# huzzah32_driver.net
KiCad netlist of a schematic drawn in EAGLE
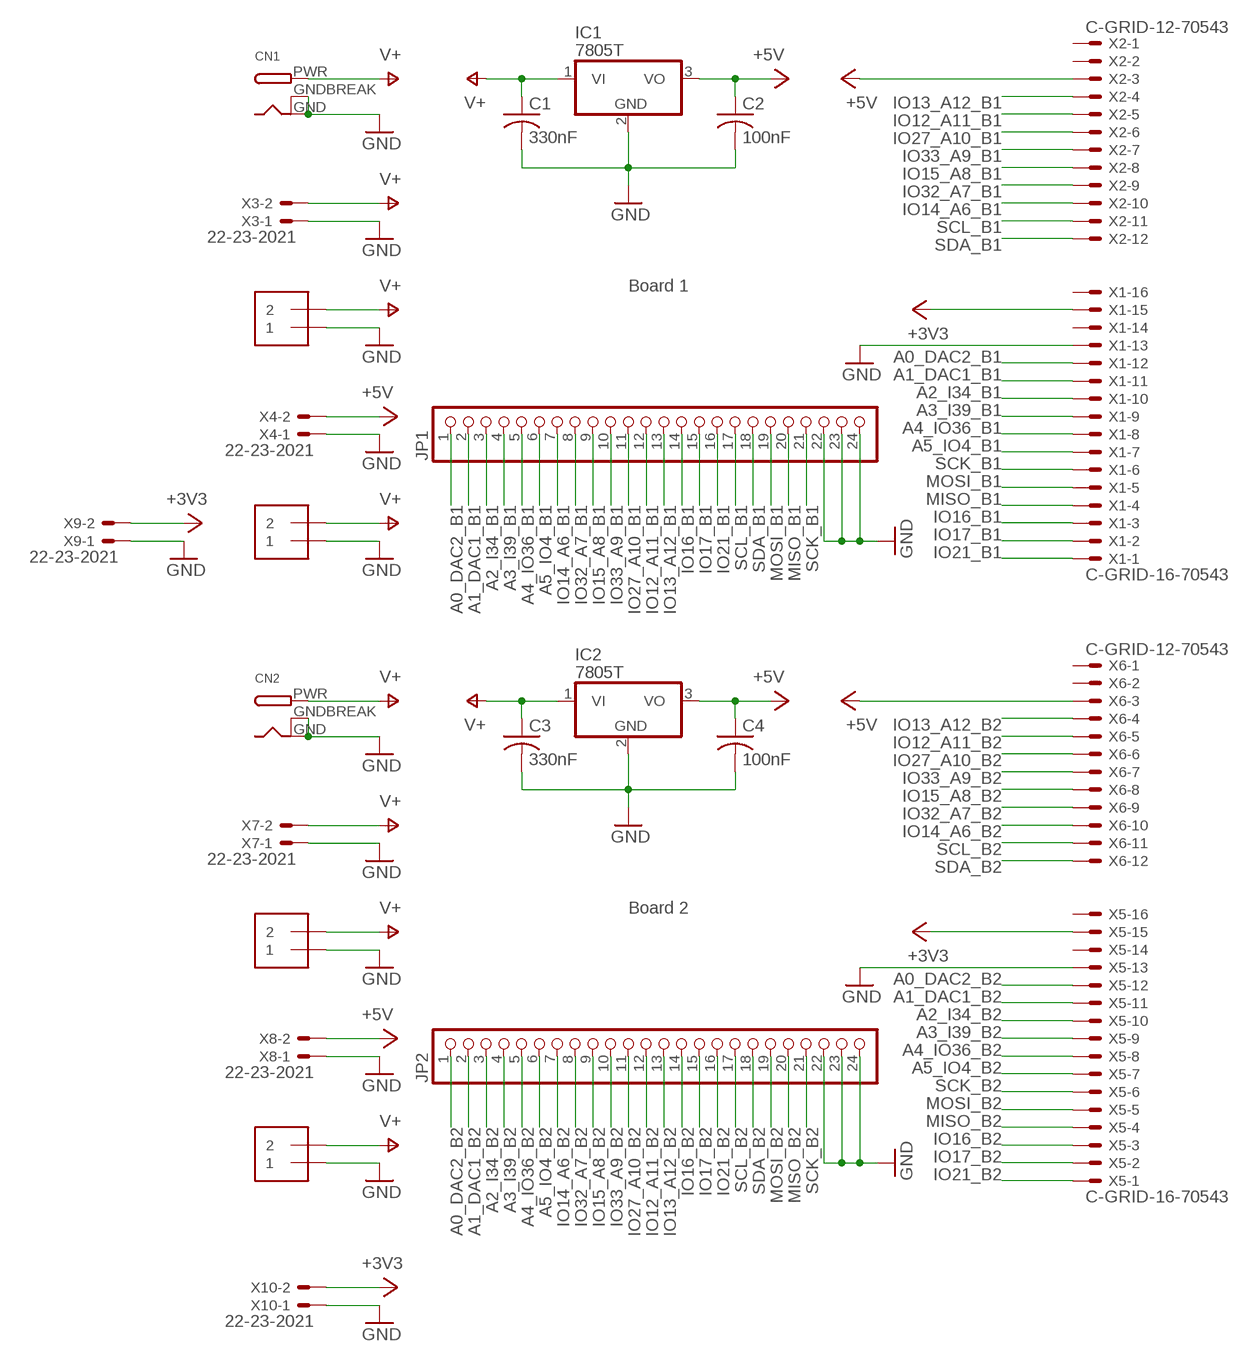
[diagram p0: schematic, sheet 1]

(export (version "E")
  (design (tool "Eeschema 10.0.6"))
  (components
    (comp (ref "C1")
      (value "330nF")
      (footprint "eagle-import:C050-035X075")
      (libsource (lib "eagle-import") (part "C-US050-035X075"))
    )
    (comp (ref "C2")
      (value "100nF")
      (footprint "eagle-import:C050-035X075")
      (libsource (lib "eagle-import") (part "C-US050-035X075"))
    )
    (comp (ref "C3")
      (value "330nF")
      (footprint "eagle-import:C050-035X075")
      (libsource (lib "eagle-import") (part "C-US050-035X075"))
    )
    (comp (ref "C4")
      (value "100nF")
      (footprint "eagle-import:C050-035X075")
      (libsource (lib "eagle-import") (part "C-US050-035X075"))
    )
    (comp (ref "CN1")
      (value "DCBARRELPTH")
      (footprint "eagle-import:DCJACK_2MM_PTH")
      (libsource (lib "eagle-import") (part "DCBARRELPTH"))
    )
    (comp (ref "CN2")
      (value "DCBARRELPTH")
      (footprint "eagle-import:DCJACK_2MM_PTH")
      (libsource (lib "eagle-import") (part "DCBARRELPTH"))
    )
    (comp (ref "IC1")
      (value "7805T")
      (footprint "eagle-import:TO220H")
      (libsource (lib "eagle-import") (part "78T05"))
    )
    (comp (ref "IC2")
      (value "7805T")
      (footprint "eagle-import:TO220H")
      (libsource (lib "eagle-import") (part "78T05"))
    )
    (comp (ref "J1")
      (value "1X2-3.5MM")
      (footprint "eagle-import:1X2-3.5MM")
      (libsource (lib "eagle-import") (part "1X2-3.5MM"))
    )
    (comp (ref "J2")
      (value "1X2-3.5MM")
      (footprint "eagle-import:1X2-3.5MM")
      (libsource (lib "eagle-import") (part "1X2-3.5MM"))
    )
    (comp (ref "J3")
      (value "1X2-3.5MM")
      (footprint "eagle-import:1X2-3.5MM")
      (libsource (lib "eagle-import") (part "1X2-3.5MM"))
    )
    (comp (ref "J4")
      (value "1X2-3.5MM")
      (footprint "eagle-import:1X2-3.5MM")
      (libsource (lib "eagle-import") (part "1X2-3.5MM"))
    )
    (comp (ref "JP1")
      (value "PINHD-1X24")
      (footprint "eagle-import:1X24")
      (libsource (lib "eagle-import") (part "PINHD-1X24"))
    )
    (comp (ref "JP2")
      (value "PINHD-1X24")
      (footprint "eagle-import:1X24")
      (libsource (lib "eagle-import") (part "PINHD-1X24"))
    )
    (comp (ref "X1")
      (value "C-GRID-16-70543")
      (footprint "eagle-import:70543-16")
      (libsource (lib "eagle-import") (part "C-GRID-16-70543"))
    )
    (comp (ref "X2")
      (value "C-GRID-12-70543")
      (footprint "eagle-import:70543-12")
      (libsource (lib "eagle-import") (part "C-GRID-12-70543"))
    )
    (comp (ref "X3")
      (value "22-23-2021")
      (footprint "eagle-import:22-23-2021")
      (fields (field (name "MF") "MOLEX"))
      (libsource (lib "eagle-import") (part "22-23-2021"))
    )
    (comp (ref "X4")
      (value "22-23-2021")
      (footprint "eagle-import:22-23-2021")
      (fields (field (name "MF") "MOLEX"))
      (libsource (lib "eagle-import") (part "22-23-2021"))
    )
    (comp (ref "X5")
      (value "C-GRID-16-70543")
      (footprint "eagle-import:70543-16")
      (libsource (lib "eagle-import") (part "C-GRID-16-70543"))
    )
    (comp (ref "X6")
      (value "C-GRID-12-70543")
      (footprint "eagle-import:70543-12")
      (libsource (lib "eagle-import") (part "C-GRID-12-70543"))
    )
    (comp (ref "X7")
      (value "22-23-2021")
      (footprint "eagle-import:22-23-2021")
      (fields (field (name "MF") "MOLEX"))
      (libsource (lib "eagle-import") (part "22-23-2021"))
    )
    (comp (ref "X8")
      (value "22-23-2021")
      (footprint "eagle-import:22-23-2021")
      (fields (field (name "MF") "MOLEX"))
      (libsource (lib "eagle-import") (part "22-23-2021"))
    )
    (comp (ref "X9")
      (value "22-23-2021")
      (footprint "eagle-import:22-23-2021")
      (fields (field (name "MF") "MOLEX"))
      (libsource (lib "eagle-import") (part "22-23-2021"))
    )
    (comp (ref "X10")
      (value "22-23-2021")
      (footprint "eagle-import:22-23-2021")
      (fields (field (name "MF") "MOLEX"))
      (libsource (lib "eagle-import") (part "22-23-2021"))
    )
  )
  (nets
    (net (code "1") (name "+3V3") (class "Default")
      (node (ref "X1") (pin "15") (pinfunction "S_15") (pintype "passive"))
      (node (ref "X10") (pin "2") (pinfunction "S_2") (pintype "passive"))
      (node (ref "X5") (pin "15") (pinfunction "S_15") (pintype "passive"))
      (node (ref "X9") (pin "2") (pinfunction "S_2") (pintype "passive"))
    )
    (net (code "2") (name "+5V") (class "Default")
      (node (ref "C2") (pin "1") (pinfunction "1_1") (pintype "passive"))
      (node (ref "C4") (pin "1") (pinfunction "1_1") (pintype "passive"))
      (node (ref "IC1") (pin "3") (pinfunction "VO_3") (pintype "passive"))
      (node (ref "IC2") (pin "3") (pinfunction "VO_3") (pintype "passive"))
      (node (ref "X2") (pin "3") (pinfunction "S_3") (pintype "passive"))
      (node (ref "X4") (pin "2") (pinfunction "S_2") (pintype "passive"))
      (node (ref "X6") (pin "3") (pinfunction "S_3") (pintype "passive"))
      (node (ref "X8") (pin "2") (pinfunction "S_2") (pintype "passive"))
    )
    (net (code "3") (name "/A0_DAC2_B1") (class "Default")
      (node (ref "JP1") (pin "1") (pinfunction "1_1") (pintype "passive"))
      (node (ref "X1") (pin "12") (pinfunction "S_12") (pintype "passive"))
    )
    (net (code "4") (name "/A0_DAC2_B2") (class "Default")
      (node (ref "JP2") (pin "1") (pinfunction "1_1") (pintype "passive"))
      (node (ref "X5") (pin "12") (pinfunction "S_12") (pintype "passive"))
    )
    (net (code "5") (name "/A1_DAC1_B1") (class "Default")
      (node (ref "JP1") (pin "2") (pinfunction "2_2") (pintype "passive"))
      (node (ref "X1") (pin "11") (pinfunction "S_11") (pintype "passive"))
    )
    (net (code "6") (name "/A1_DAC1_B2") (class "Default")
      (node (ref "JP2") (pin "2") (pinfunction "2_2") (pintype "passive"))
      (node (ref "X5") (pin "11") (pinfunction "S_11") (pintype "passive"))
    )
    (net (code "7") (name "/A2_I34_B1") (class "Default")
      (node (ref "JP1") (pin "3") (pinfunction "3_3") (pintype "passive"))
      (node (ref "X1") (pin "10") (pinfunction "S_10") (pintype "passive"))
    )
    (net (code "8") (name "/A2_I34_B2") (class "Default")
      (node (ref "JP2") (pin "3") (pinfunction "3_3") (pintype "passive"))
      (node (ref "X5") (pin "10") (pinfunction "S_10") (pintype "passive"))
    )
    (net (code "9") (name "/A3_I39_B1") (class "Default")
      (node (ref "JP1") (pin "4") (pinfunction "4_4") (pintype "passive"))
      (node (ref "X1") (pin "9") (pinfunction "S_9") (pintype "passive"))
    )
    (net (code "10") (name "/A3_I39_B2") (class "Default")
      (node (ref "JP2") (pin "4") (pinfunction "4_4") (pintype "passive"))
      (node (ref "X5") (pin "9") (pinfunction "S_9") (pintype "passive"))
    )
    (net (code "11") (name "/A4_IO36_B1") (class "Default")
      (node (ref "JP1") (pin "5") (pinfunction "5_5") (pintype "passive"))
      (node (ref "X1") (pin "8") (pinfunction "S_8") (pintype "passive"))
    )
    (net (code "12") (name "/A4_IO36_B2") (class "Default")
      (node (ref "JP2") (pin "5") (pinfunction "5_5") (pintype "passive"))
      (node (ref "X5") (pin "8") (pinfunction "S_8") (pintype "passive"))
    )
    (net (code "13") (name "/A5_IO4_B1") (class "Default")
      (node (ref "JP1") (pin "6") (pinfunction "6_6") (pintype "passive"))
      (node (ref "X1") (pin "7") (pinfunction "S_7") (pintype "passive"))
    )
    (net (code "14") (name "/A5_IO4_B2") (class "Default")
      (node (ref "JP2") (pin "6") (pinfunction "6_6") (pintype "passive"))
      (node (ref "X5") (pin "7") (pinfunction "S_7") (pintype "passive"))
    )
    (net (code "15") (name "/IO12_A11_B1") (class "Default")
      (node (ref "JP1") (pin "12") (pinfunction "12_12") (pintype "passive"))
      (node (ref "X2") (pin "5") (pinfunction "S_5") (pintype "passive"))
    )
    (net (code "16") (name "/IO12_A11_B2") (class "Default")
      (node (ref "JP2") (pin "12") (pinfunction "12_12") (pintype "passive"))
      (node (ref "X6") (pin "5") (pinfunction "S_5") (pintype "passive"))
    )
    (net (code "17") (name "/IO13_A12_B1") (class "Default")
      (node (ref "JP1") (pin "13") (pinfunction "13_13") (pintype "passive"))
      (node (ref "X2") (pin "4") (pinfunction "S_4") (pintype "passive"))
    )
    (net (code "18") (name "/IO13_A12_B2") (class "Default")
      (node (ref "JP2") (pin "13") (pinfunction "13_13") (pintype "passive"))
      (node (ref "X6") (pin "4") (pinfunction "S_4") (pintype "passive"))
    )
    (net (code "19") (name "/IO14_A6_B1") (class "Default")
      (node (ref "JP1") (pin "7") (pinfunction "7_7") (pintype "passive"))
      (node (ref "X2") (pin "10") (pinfunction "S_10") (pintype "passive"))
    )
    (net (code "20") (name "/IO14_A6_B2") (class "Default")
      (node (ref "JP2") (pin "7") (pinfunction "7_7") (pintype "passive"))
      (node (ref "X6") (pin "10") (pinfunction "S_10") (pintype "passive"))
    )
    (net (code "21") (name "/IO15_A8_B1") (class "Default")
      (node (ref "JP1") (pin "9") (pinfunction "9_9") (pintype "passive"))
      (node (ref "X2") (pin "8") (pinfunction "S_8") (pintype "passive"))
    )
    (net (code "22") (name "/IO15_A8_B2") (class "Default")
      (node (ref "JP2") (pin "9") (pinfunction "9_9") (pintype "passive"))
      (node (ref "X6") (pin "8") (pinfunction "S_8") (pintype "passive"))
    )
    (net (code "23") (name "/IO16_B1") (class "Default")
      (node (ref "JP1") (pin "14") (pinfunction "14_14") (pintype "passive"))
      (node (ref "X1") (pin "3") (pinfunction "S_3") (pintype "passive"))
    )
    (net (code "24") (name "/IO16_B2") (class "Default")
      (node (ref "JP2") (pin "14") (pinfunction "14_14") (pintype "passive"))
      (node (ref "X5") (pin "3") (pinfunction "S_3") (pintype "passive"))
    )
    (net (code "25") (name "/IO17_B1") (class "Default")
      (node (ref "JP1") (pin "15") (pinfunction "15_15") (pintype "passive"))
      (node (ref "X1") (pin "2") (pinfunction "S_2") (pintype "passive"))
    )
    (net (code "26") (name "/IO17_B2") (class "Default")
      (node (ref "JP2") (pin "15") (pinfunction "15_15") (pintype "passive"))
      (node (ref "X5") (pin "2") (pinfunction "S_2") (pintype "passive"))
    )
    (net (code "27") (name "/IO21_B1") (class "Default")
      (node (ref "JP1") (pin "16") (pinfunction "16_16") (pintype "passive"))
      (node (ref "X1") (pin "1") (pinfunction "S_1") (pintype "passive"))
    )
    (net (code "28") (name "/IO21_B2") (class "Default")
      (node (ref "JP2") (pin "16") (pinfunction "16_16") (pintype "passive"))
      (node (ref "X5") (pin "1") (pinfunction "S_1") (pintype "passive"))
    )
    (net (code "29") (name "/IO27_A10_B1") (class "Default")
      (node (ref "JP1") (pin "11") (pinfunction "11_11") (pintype "passive"))
      (node (ref "X2") (pin "6") (pinfunction "S_6") (pintype "passive"))
    )
    (net (code "30") (name "/IO27_A10_B2") (class "Default")
      (node (ref "JP2") (pin "11") (pinfunction "11_11") (pintype "passive"))
      (node (ref "X6") (pin "6") (pinfunction "S_6") (pintype "passive"))
    )
    (net (code "31") (name "/IO32_A7_B1") (class "Default")
      (node (ref "JP1") (pin "8") (pinfunction "8_8") (pintype "passive"))
      (node (ref "X2") (pin "9") (pinfunction "S_9") (pintype "passive"))
    )
    (net (code "32") (name "/IO32_A7_B2") (class "Default")
      (node (ref "JP2") (pin "8") (pinfunction "8_8") (pintype "passive"))
      (node (ref "X6") (pin "9") (pinfunction "S_9") (pintype "passive"))
    )
    (net (code "33") (name "/IO33_A9_B1") (class "Default")
      (node (ref "JP1") (pin "10") (pinfunction "10_10") (pintype "passive"))
      (node (ref "X2") (pin "7") (pinfunction "S_7") (pintype "passive"))
    )
    (net (code "34") (name "/IO33_A9_B2") (class "Default")
      (node (ref "JP2") (pin "10") (pinfunction "10_10") (pintype "passive"))
      (node (ref "X6") (pin "7") (pinfunction "S_7") (pintype "passive"))
    )
    (net (code "35") (name "/MISO_B1") (class "Default")
      (node (ref "JP1") (pin "20") (pinfunction "20_20") (pintype "passive"))
      (node (ref "X1") (pin "4") (pinfunction "S_4") (pintype "passive"))
    )
    (net (code "36") (name "/MISO_B2") (class "Default")
      (node (ref "JP2") (pin "20") (pinfunction "20_20") (pintype "passive"))
      (node (ref "X5") (pin "4") (pinfunction "S_4") (pintype "passive"))
    )
    (net (code "37") (name "/MOSI_B1") (class "Default")
      (node (ref "JP1") (pin "19") (pinfunction "19_19") (pintype "passive"))
      (node (ref "X1") (pin "5") (pinfunction "S_5") (pintype "passive"))
    )
    (net (code "38") (name "/MOSI_B2") (class "Default")
      (node (ref "JP2") (pin "19") (pinfunction "19_19") (pintype "passive"))
      (node (ref "X5") (pin "5") (pinfunction "S_5") (pintype "passive"))
    )
    (net (code "39") (name "/SCK_B1") (class "Default")
      (node (ref "JP1") (pin "21") (pinfunction "21_21") (pintype "passive"))
      (node (ref "X1") (pin "6") (pinfunction "S_6") (pintype "passive"))
    )
    (net (code "40") (name "/SCK_B2") (class "Default")
      (node (ref "JP2") (pin "21") (pinfunction "21_21") (pintype "passive"))
      (node (ref "X5") (pin "6") (pinfunction "S_6") (pintype "passive"))
    )
    (net (code "41") (name "/SCL_B1") (class "Default")
      (node (ref "JP1") (pin "17") (pinfunction "17_17") (pintype "passive"))
      (node (ref "X2") (pin "11") (pinfunction "S_11") (pintype "passive"))
    )
    (net (code "42") (name "/SCL_B2") (class "Default")
      (node (ref "JP2") (pin "17") (pinfunction "17_17") (pintype "passive"))
      (node (ref "X6") (pin "11") (pinfunction "S_11") (pintype "passive"))
    )
    (net (code "43") (name "/SDA_B1") (class "Default")
      (node (ref "JP1") (pin "18") (pinfunction "18_18") (pintype "passive"))
      (node (ref "X2") (pin "12") (pinfunction "S_12") (pintype "passive"))
    )
    (net (code "44") (name "/SDA_B2") (class "Default")
      (node (ref "JP2") (pin "18") (pinfunction "18_18") (pintype "passive"))
      (node (ref "X6") (pin "12") (pinfunction "S_12") (pintype "passive"))
    )
    (net (code "45") (name "GND") (class "Default")
      (node (ref "C1") (pin "2") (pinfunction "2_2") (pintype "passive"))
      (node (ref "C2") (pin "2") (pinfunction "2_2") (pintype "passive"))
      (node (ref "C3") (pin "2") (pinfunction "2_2") (pintype "passive"))
      (node (ref "C4") (pin "2") (pinfunction "2_2") (pintype "passive"))
      (node (ref "CN1") (pin "GND") (pinfunction "GND_GND") (pintype "power_in"))
      (node (ref "CN1") (pin "GNDBREAK") (pinfunction "GNDBREAK_GNDBREAK") (pintype "power_in"))
      (node (ref "CN2") (pin "GND") (pinfunction "GND_GND") (pintype "power_in"))
      (node (ref "CN2") (pin "GNDBREAK") (pinfunction "GNDBREAK_GNDBREAK") (pintype "power_in"))
      (node (ref "IC1") (pin "2") (pinfunction "GND_2") (pintype "passive"))
      (node (ref "IC2") (pin "2") (pinfunction "GND_2") (pintype "passive"))
      (node (ref "J1") (pin "1") (pinfunction "1_1") (pintype "passive"))
      (node (ref "J2") (pin "1") (pinfunction "1_1") (pintype "passive"))
      (node (ref "J3") (pin "1") (pinfunction "1_1") (pintype "passive"))
      (node (ref "J4") (pin "1") (pinfunction "1_1") (pintype "passive"))
      (node (ref "JP1") (pin "22") (pinfunction "22_22") (pintype "passive"))
      (node (ref "JP1") (pin "23") (pinfunction "23_23") (pintype "passive"))
      (node (ref "JP1") (pin "24") (pinfunction "24_24") (pintype "passive"))
      (node (ref "JP2") (pin "22") (pinfunction "22_22") (pintype "passive"))
      (node (ref "JP2") (pin "23") (pinfunction "23_23") (pintype "passive"))
      (node (ref "JP2") (pin "24") (pinfunction "24_24") (pintype "passive"))
      (node (ref "X1") (pin "13") (pinfunction "S_13") (pintype "passive"))
      (node (ref "X10") (pin "1") (pinfunction "S_1") (pintype "passive"))
      (node (ref "X3") (pin "1") (pinfunction "S_1") (pintype "passive"))
      (node (ref "X4") (pin "1") (pinfunction "S_1") (pintype "passive"))
      (node (ref "X5") (pin "13") (pinfunction "S_13") (pintype "passive"))
      (node (ref "X7") (pin "1") (pinfunction "S_1") (pintype "passive"))
      (node (ref "X8") (pin "1") (pinfunction "S_1") (pintype "passive"))
      (node (ref "X9") (pin "1") (pinfunction "S_1") (pintype "passive"))
    )
    (net (code "46") (name "V+") (class "Default")
      (node (ref "C1") (pin "1") (pinfunction "1_1") (pintype "passive"))
      (node (ref "C3") (pin "1") (pinfunction "1_1") (pintype "passive"))
      (node (ref "CN1") (pin "PWR") (pinfunction "PWR_PWR") (pintype "power_in"))
      (node (ref "CN2") (pin "PWR") (pinfunction "PWR_PWR") (pintype "power_in"))
      (node (ref "IC1") (pin "1") (pinfunction "VI_1") (pintype "input"))
      (node (ref "IC2") (pin "1") (pinfunction "VI_1") (pintype "input"))
      (node (ref "J1") (pin "2") (pinfunction "2_2") (pintype "passive"))
      (node (ref "J2") (pin "2") (pinfunction "2_2") (pintype "passive"))
      (node (ref "J3") (pin "2") (pinfunction "2_2") (pintype "passive"))
      (node (ref "J4") (pin "2") (pinfunction "2_2") (pintype "passive"))
      (node (ref "X3") (pin "2") (pinfunction "S_2") (pintype "passive"))
      (node (ref "X7") (pin "2") (pinfunction "S_2") (pintype "passive"))
    )
    (net (code "47") (name "unconnected-(X1F-S-Pad14)") (class "Default")
      (node (ref "X1") (pin "14") (pinfunction "S_14") (pintype "passive"))
    )
    (net (code "48") (name "unconnected-(X1H-S-Pad16)") (class "Default")
      (node (ref "X1") (pin "16") (pinfunction "S_16") (pintype "passive"))
    )
    (net (code "49") (name "unconnected-(X2A-S-Pad1)") (class "Default")
      (node (ref "X2") (pin "1") (pinfunction "S_1") (pintype "passive"))
    )
    (net (code "50") (name "unconnected-(X2E-S-Pad2)") (class "Default")
      (node (ref "X2") (pin "2") (pinfunction "S_2") (pintype "passive"))
    )
    (net (code "51") (name "unconnected-(X5F-S-Pad14)") (class "Default")
      (node (ref "X5") (pin "14") (pinfunction "S_14") (pintype "passive"))
    )
    (net (code "52") (name "unconnected-(X5H-S-Pad16)") (class "Default")
      (node (ref "X5") (pin "16") (pinfunction "S_16") (pintype "passive"))
    )
    (net (code "53") (name "unconnected-(X6A-S-Pad1)") (class "Default")
      (node (ref "X6") (pin "1") (pinfunction "S_1") (pintype "passive"))
    )
    (net (code "54") (name "unconnected-(X6E-S-Pad2)") (class "Default")
      (node (ref "X6") (pin "2") (pinfunction "S_2") (pintype "passive"))
    )
  )
)
